# CMOS_MUX.net
KiCad netlist of a schematic drawn in Altium Designer
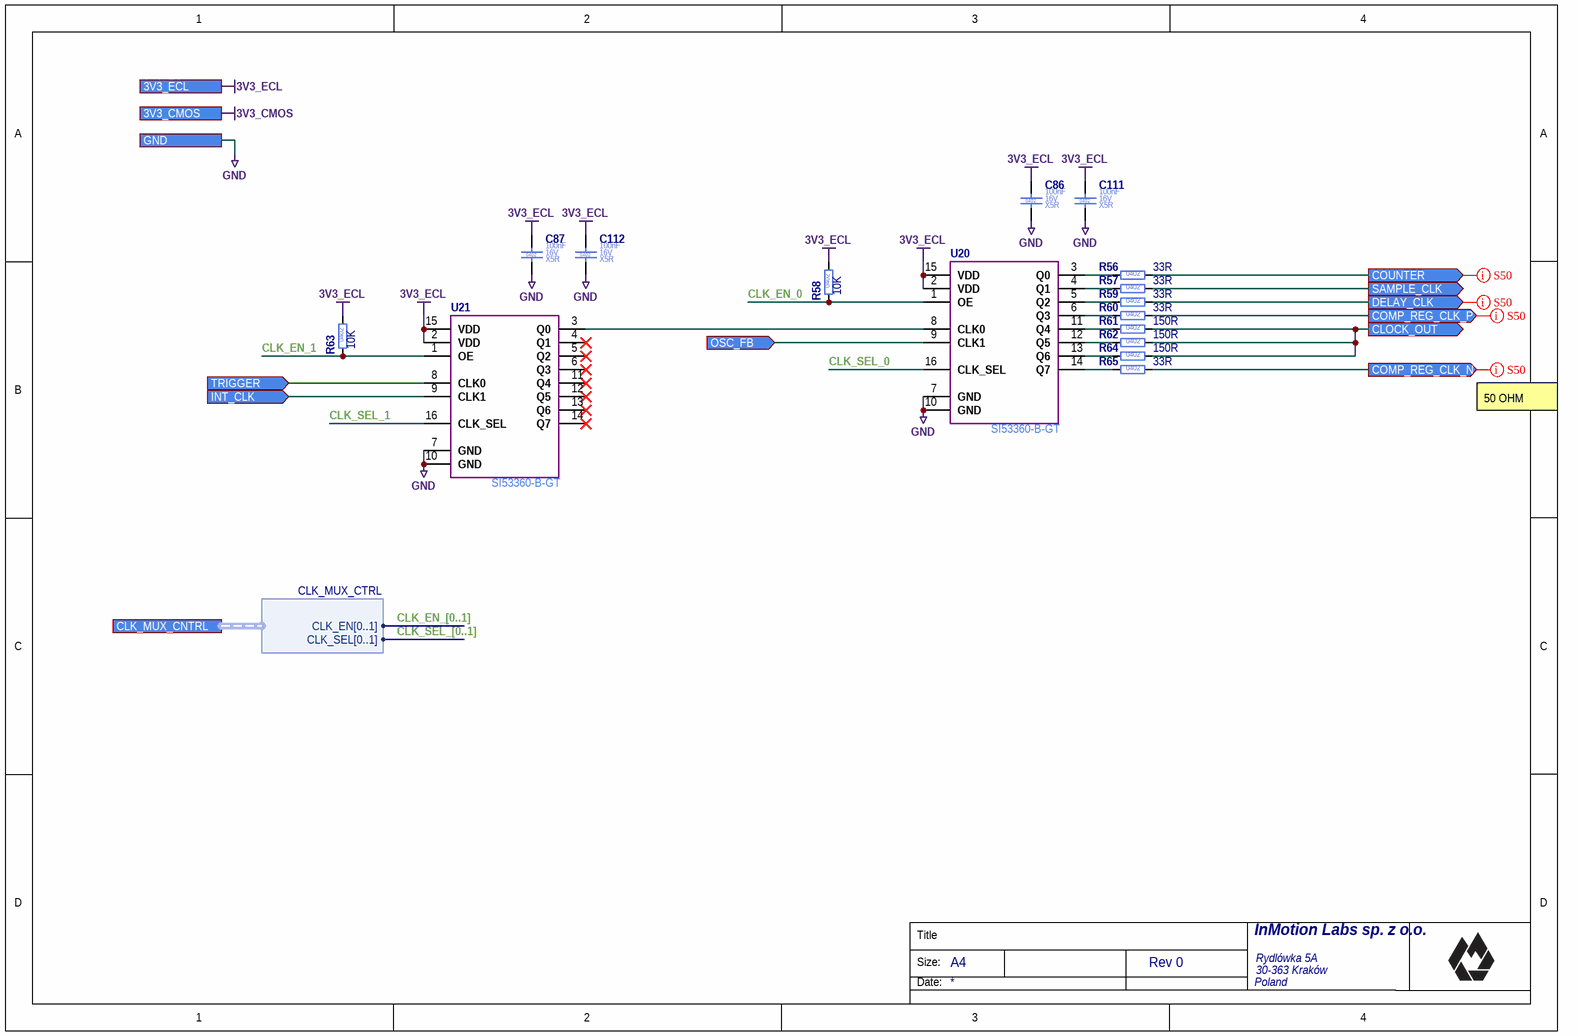
[diagram p0: CMOS_MUX.SchDoc]

(export (version "E")
  (design (tool "Eeschema 10.0.6"))
  (components
    (comp (ref "C86")
      (value "C_100NF_16V_X5R_0402_10")
      (footprint "C_0402_1005")
      (description "Ceramic Capacitor")
      (fields
        (field (name "CASE/PACKAGE") "0402")
        (field (name "VOLTAGE RATING (DC)") "16V")
        (field (name "DIELECTRIC") "X5R")
        (field (name "CAPACITANCE") "100nF")
        (field (name "TOLERANCE") "10%")
        (field (name "MANUFACTURER PART NUMBER") "EMK105BJ104KV-F")
      )
      (libsource (lib "7Sigma") (part "C"))
    )
    (comp (ref "C87")
      (value "C_100NF_16V_X5R_0402_10")
      (footprint "C_0402_1005")
      (description "Ceramic Capacitor")
      (fields
        (field (name "CASE/PACKAGE") "0402")
        (field (name "VOLTAGE RATING (DC)") "16V")
        (field (name "DIELECTRIC") "X5R")
        (field (name "CAPACITANCE") "100nF")
        (field (name "TOLERANCE") "10%")
        (field (name "MANUFACTURER PART NUMBER") "EMK105BJ104KV-F")
      )
      (libsource (lib "7Sigma") (part "C"))
    )
    (comp (ref "C111")
      (value "C_100NF_16V_X5R_0402_10")
      (footprint "C_0402_1005")
      (description "Ceramic Capacitor")
      (fields
        (field (name "CASE/PACKAGE") "0402")
        (field (name "VOLTAGE RATING (DC)") "16V")
        (field (name "DIELECTRIC") "X5R")
        (field (name "CAPACITANCE") "100nF")
        (field (name "TOLERANCE") "10%")
        (field (name "MANUFACTURER PART NUMBER") "EMK105BJ104KV-F")
      )
      (libsource (lib "7Sigma") (part "C"))
    )
    (comp (ref "C112")
      (value "C_100NF_16V_X5R_0402_10")
      (footprint "C_0402_1005")
      (description "Ceramic Capacitor")
      (fields
        (field (name "CASE/PACKAGE") "0402")
        (field (name "VOLTAGE RATING (DC)") "16V")
        (field (name "DIELECTRIC") "X5R")
        (field (name "CAPACITANCE") "100nF")
        (field (name "TOLERANCE") "10%")
        (field (name "MANUFACTURER PART NUMBER") "EMK105BJ104KV-F")
      )
      (libsource (lib "7Sigma") (part "C"))
    )
    (comp (ref "R56")
      (value "R_33R_0402_1")
      (footprint "R_0402_1005")
      (description "Thick Film Resistor")
      (fields
        (field (name "RESISTANCE") "33R")
        (field (name "CASE/PACKAGE") "0402")
        (field (name "TOLERANCE") "1%")
        (field (name "MANUFACTURER") "Yageo")
      )
      (libsource (lib "7Sigma") (part "R"))
    )
    (comp (ref "R57")
      (value "R_33R_0402_1")
      (footprint "R_0402_1005")
      (description "Thick Film Resistor")
      (fields
        (field (name "RESISTANCE") "33R")
        (field (name "CASE/PACKAGE") "0402")
        (field (name "TOLERANCE") "1%")
        (field (name "MANUFACTURER") "Yageo")
      )
      (libsource (lib "7Sigma") (part "R"))
    )
    (comp (ref "R58")
      (value "R_10K_0402_1")
      (footprint "R_0402_1005")
      (description "Thick Film Resistor")
      (fields
        (field (name "RESISTANCE") "10K")
        (field (name "CASE/PACKAGE") "0402")
        (field (name "TOLERANCE") "1%")
        (field (name "MANUFACTURER") "Yageo")
      )
      (libsource (lib "7Sigma") (part "R"))
    )
    (comp (ref "R59")
      (value "R_33R_0402_1")
      (footprint "R_0402_1005")
      (description "Thick Film Resistor")
      (fields
        (field (name "RESISTANCE") "33R")
        (field (name "CASE/PACKAGE") "0402")
        (field (name "TOLERANCE") "1%")
        (field (name "MANUFACTURER") "Yageo")
      )
      (libsource (lib "7Sigma") (part "R"))
    )
    (comp (ref "R60")
      (value "R_33R_0402_1")
      (footprint "R_0402_1005")
      (description "Thick Film Resistor")
      (fields
        (field (name "RESISTANCE") "33R")
        (field (name "CASE/PACKAGE") "0402")
        (field (name "TOLERANCE") "1%")
        (field (name "MANUFACTURER") "Yageo")
      )
      (libsource (lib "7Sigma") (part "R"))
    )
    (comp (ref "R61")
      (value "R_150R_0402_1")
      (footprint "R_0402_1005")
      (description "Thick Film Resistor")
      (fields
        (field (name "RESISTANCE") "150R")
        (field (name "CASE/PACKAGE") "0402")
        (field (name "TOLERANCE") "1%")
        (field (name "MANUFACTURER") "Yageo")
      )
      (libsource (lib "7Sigma") (part "R"))
    )
    (comp (ref "R62")
      (value "R_150R_0402_1")
      (footprint "R_0402_1005")
      (description "Thick Film Resistor")
      (fields
        (field (name "RESISTANCE") "150R")
        (field (name "CASE/PACKAGE") "0402")
        (field (name "TOLERANCE") "1%")
        (field (name "MANUFACTURER") "Yageo")
      )
      (libsource (lib "7Sigma") (part "R"))
    )
    (comp (ref "R63")
      (value "R_10K_0402_1")
      (footprint "R_0402_1005")
      (description "Thick Film Resistor")
      (fields
        (field (name "RESISTANCE") "10K")
        (field (name "CASE/PACKAGE") "0402")
        (field (name "TOLERANCE") "1%")
        (field (name "MANUFACTURER") "Yageo")
      )
      (libsource (lib "7Sigma") (part "R"))
    )
    (comp (ref "R64")
      (value "R_150R_0402_1")
      (footprint "R_0402_1005")
      (description "Thick Film Resistor")
      (fields
        (field (name "RESISTANCE") "150R")
        (field (name "CASE/PACKAGE") "0402")
        (field (name "TOLERANCE") "1%")
        (field (name "MANUFACTURER") "Yageo")
      )
      (libsource (lib "7Sigma") (part "R"))
    )
    (comp (ref "R65")
      (value "R_33R_0402_1")
      (footprint "R_0402_1005")
      (description "Thick Film Resistor")
      (fields
        (field (name "RESISTANCE") "33R")
        (field (name "CASE/PACKAGE") "0402")
        (field (name "TOLERANCE") "1%")
        (field (name "MANUFACTURER") "Yageo")
      )
      (libsource (lib "7Sigma") (part "R"))
    )
    (comp (ref "U20")
      (value "Si53360-B-GT")
      (footprint "TSOP65P640X120-16N")
      (description "Low Jitter Clock Buffer")
      (fields
        (field (name "MANUFACTURER") "Silicon Labs")
        (field (name "MANUFACTURER PART NUMBER") "SI53360-B-GT")
      )
      (libsource (lib "7Sigma") (part "Si53360-B-GT"))
    )
    (comp (ref "U21")
      (value "Si53360-B-GT")
      (footprint "TSOP65P640X120-16N")
      (description "Low Jitter Clock Buffer")
      (fields
        (field (name "MANUFACTURER") "Silicon Labs")
        (field (name "MANUFACTURER PART NUMBER") "SI53360-B-GT")
      )
      (libsource (lib "7Sigma") (part "Si53360-B-GT"))
    )
  )
  (nets
    (net (code "2") (name "/CLK_EN_0") (class "Default")
      (node (ref "R58") (pin "1") (pinfunction "1_1") (pintype "passive"))
      (node (ref "U20") (pin "1") (pinfunction "OE_1") (pintype "passive"))
    )
    (net (code "3") (name "/CLK_EN_1") (class "Default")
      (node (ref "R63") (pin "1") (pinfunction "1_1") (pintype "passive"))
      (node (ref "U21") (pin "1") (pinfunction "OE_1") (pintype "passive"))
    )
    (net (code "5") (name "/CLK_SEL_0") (class "Default")
      (node (ref "U20") (pin "16") (pinfunction "CLK_SEL_16") (pintype "passive"))
    )
    (net (code "6") (name "/CLK_SEL_1") (class "Default")
      (node (ref "U21") (pin "16") (pinfunction "CLK_SEL_16") (pintype "passive"))
    )
    (net (code "8") (name "/CLOCK_OUT") (class "Default")
      (node (ref "R61") (pin "2") (pinfunction "2_2") (pintype "passive"))
      (node (ref "R62") (pin "2") (pinfunction "2_2") (pintype "passive"))
      (node (ref "R64") (pin "2") (pinfunction "2_2") (pintype "passive"))
    )
    (net (code "9") (name "/COMP_REG_CLK_N") (class "Default")
      (node (ref "R65") (pin "2") (pinfunction "2_2") (pintype "passive"))
    )
    (net (code "10") (name "/COMP_REG_CLK_P") (class "Default")
      (node (ref "R60") (pin "2") (pinfunction "2_2") (pintype "passive"))
    )
    (net (code "11") (name "/COUNTER") (class "Default")
      (node (ref "R56") (pin "2") (pinfunction "2_2") (pintype "passive"))
    )
    (net (code "12") (name "/DELAY_CLK") (class "Default")
      (node (ref "R59") (pin "2") (pinfunction "2_2") (pintype "passive"))
    )
    (net (code "13") (name "/INT_CLK") (class "Default")
      (node (ref "U21") (pin "9") (pinfunction "CLK1_9") (pintype "passive"))
    )
    (net (code "14") (name "/OSC_FB") (class "Default")
      (node (ref "U20") (pin "9") (pinfunction "CLK1_9") (pintype "passive"))
    )
    (net (code "15") (name "/SAMPLE_CLK") (class "Default")
      (node (ref "R57") (pin "2") (pinfunction "2_2") (pintype "passive"))
    )
    (net (code "16") (name "/TRIGGER") (class "Default")
      (node (ref "U21") (pin "8") (pinfunction "CLK0_8") (pintype "passive"))
    )
    (net (code "19") (name "3V3_ECL") (class "Default")
      (node (ref "C111") (pin "1") (pinfunction "1_1") (pintype "passive"))
      (node (ref "C112") (pin "1") (pinfunction "1_1") (pintype "passive"))
      (node (ref "C86") (pin "1") (pinfunction "1_1") (pintype "passive"))
      (node (ref "C87") (pin "1") (pinfunction "1_1") (pintype "passive"))
      (node (ref "R58") (pin "2") (pinfunction "2_2") (pintype "passive"))
      (node (ref "R63") (pin "2") (pinfunction "2_2") (pintype "passive"))
      (node (ref "U20") (pin "15") (pinfunction "VDD_15") (pintype "passive"))
      (node (ref "U20") (pin "2") (pinfunction "VDD_2") (pintype "passive"))
      (node (ref "U21") (pin "15") (pinfunction "VDD_15") (pintype "passive"))
      (node (ref "U21") (pin "2") (pinfunction "VDD_2") (pintype "passive"))
    )
    (net (code "20") (name "GND") (class "Default")
      (node (ref "C111") (pin "2") (pinfunction "2_2") (pintype "passive"))
      (node (ref "C112") (pin "2") (pinfunction "2_2") (pintype "passive"))
      (node (ref "C86") (pin "2") (pinfunction "2_2") (pintype "passive"))
      (node (ref "C87") (pin "2") (pinfunction "2_2") (pintype "passive"))
      (node (ref "U20") (pin "10") (pinfunction "GND_10") (pintype "passive"))
      (node (ref "U20") (pin "7") (pinfunction "GND_7") (pintype "passive"))
      (node (ref "U21") (pin "10") (pinfunction "GND_10") (pintype "passive"))
      (node (ref "U21") (pin "7") (pinfunction "GND_7") (pintype "passive"))
    )
    (net (code "21") (name "Net-(U20-CLK0)") (class "Default")
      (node (ref "U20") (pin "8") (pinfunction "CLK0_8") (pintype "passive"))
      (node (ref "U21") (pin "3") (pinfunction "Q0_3") (pintype "passive"))
    )
    (net (code "22") (name "Net-(U20-Q0)") (class "Default")
      (node (ref "R56") (pin "1") (pinfunction "1_1") (pintype "passive"))
      (node (ref "U20") (pin "3") (pinfunction "Q0_3") (pintype "passive"))
    )
    (net (code "23") (name "Net-(U20-Q1)") (class "Default")
      (node (ref "R57") (pin "1") (pinfunction "1_1") (pintype "passive"))
      (node (ref "U20") (pin "4") (pinfunction "Q1_4") (pintype "passive"))
    )
    (net (code "24") (name "Net-(U20-Q2)") (class "Default")
      (node (ref "R59") (pin "1") (pinfunction "1_1") (pintype "passive"))
      (node (ref "U20") (pin "5") (pinfunction "Q2_5") (pintype "passive"))
    )
    (net (code "25") (name "Net-(U20-Q3)") (class "Default")
      (node (ref "R60") (pin "1") (pinfunction "1_1") (pintype "passive"))
      (node (ref "U20") (pin "6") (pinfunction "Q3_6") (pintype "passive"))
    )
    (net (code "26") (name "Net-(U20-Q4)") (class "Default")
      (node (ref "R61") (pin "1") (pinfunction "1_1") (pintype "passive"))
      (node (ref "U20") (pin "11") (pinfunction "Q4_11") (pintype "passive"))
    )
    (net (code "27") (name "Net-(U20-Q5)") (class "Default")
      (node (ref "R62") (pin "1") (pinfunction "1_1") (pintype "passive"))
      (node (ref "U20") (pin "12") (pinfunction "Q5_12") (pintype "passive"))
    )
    (net (code "28") (name "Net-(U20-Q6)") (class "Default")
      (node (ref "R64") (pin "1") (pinfunction "1_1") (pintype "passive"))
      (node (ref "U20") (pin "13") (pinfunction "Q6_13") (pintype "passive"))
    )
    (net (code "29") (name "Net-(U20-Q7)") (class "Default")
      (node (ref "R65") (pin "1") (pinfunction "1_1") (pintype "passive"))
      (node (ref "U20") (pin "14") (pinfunction "Q7_14") (pintype "passive"))
    )
    (net (code "30") (name "unconnected-(U21-Q1-Pad4)") (class "Default")
      (node (ref "U21") (pin "4") (pinfunction "Q1_4") (pintype "passive+no_connect"))
    )
    (net (code "31") (name "unconnected-(U21-Q2-Pad5)") (class "Default")
      (node (ref "U21") (pin "5") (pinfunction "Q2_5") (pintype "passive+no_connect"))
    )
    (net (code "32") (name "unconnected-(U21-Q3-Pad6)") (class "Default")
      (node (ref "U21") (pin "6") (pinfunction "Q3_6") (pintype "passive+no_connect"))
    )
    (net (code "33") (name "unconnected-(U21-Q4-Pad11)") (class "Default")
      (node (ref "U21") (pin "11") (pinfunction "Q4_11") (pintype "passive+no_connect"))
    )
    (net (code "34") (name "unconnected-(U21-Q5-Pad12)") (class "Default")
      (node (ref "U21") (pin "12") (pinfunction "Q5_12") (pintype "passive+no_connect"))
    )
    (net (code "35") (name "unconnected-(U21-Q6-Pad13)") (class "Default")
      (node (ref "U21") (pin "13") (pinfunction "Q6_13") (pintype "passive+no_connect"))
    )
    (net (code "36") (name "unconnected-(U21-Q7-Pad14)") (class "Default")
      (node (ref "U21") (pin "14") (pinfunction "Q7_14") (pintype "passive+no_connect"))
    )
  )
)
